# THERMO.net
KiCad netlist of a schematic drawn in Altium Designer
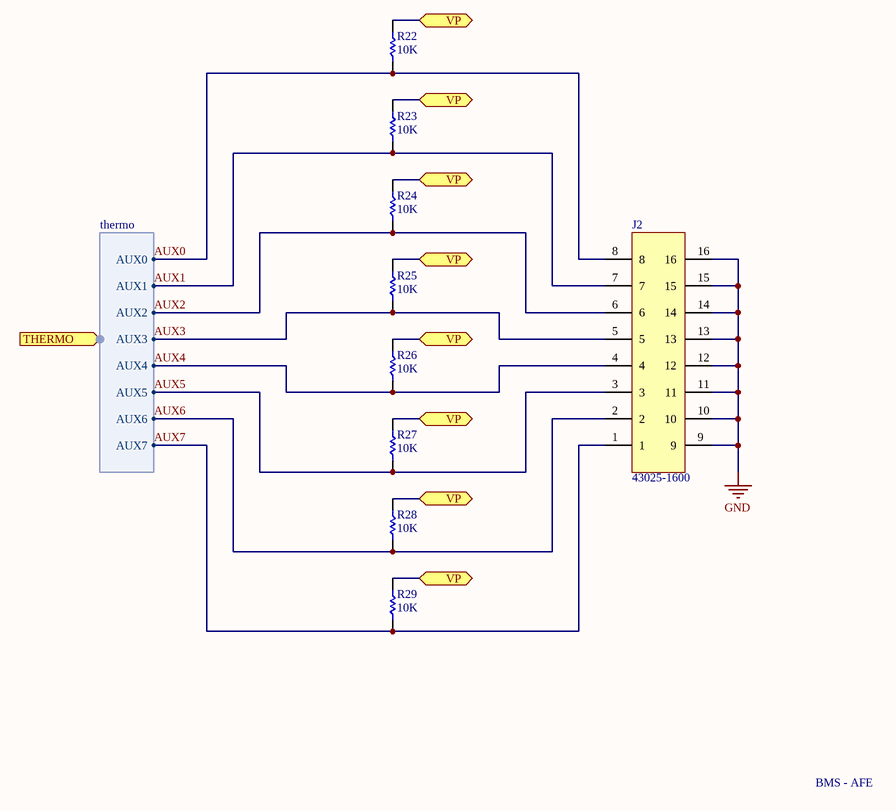
[diagram p0: THERMO.SchDoc]

(export (version "E")
  (design (tool "Eeschema 10.0.6"))
  (components
    (comp (ref "J2")
      (value "43025-1600")
      (footprint "THERMO HDR")
      (description "CONN RECEPT 16POS 3MM DUAL ROW")
      (fields (field (name "MANUFACTURER") "Molex"))
      (libsource (lib "parts") (part "43025-1600"))
    )
    (comp (ref "R22")
      (value "10K")
      (footprint "0603 RES")
      (description "RES SMD 10K OHM 1% 1/10W 0603")
      (fields
        (field (name "MANUFACTURER") "Panasonic")
        (field (name "MANUFACTURER PART NUMBER") "ERJ-3EKF1002V")
      )
      (libsource (lib "parts") (part "ERJ-3EKF1002V"))
    )
    (comp (ref "R23")
      (value "10K")
      (footprint "0603 RES")
      (description "RES SMD 10K OHM 1% 1/10W 0603")
      (fields
        (field (name "MANUFACTURER") "Panasonic")
        (field (name "MANUFACTURER PART NUMBER") "ERJ-3EKF1002V")
      )
      (libsource (lib "parts") (part "ERJ-3EKF1002V"))
    )
    (comp (ref "R24")
      (value "10K")
      (footprint "0603 RES")
      (description "RES SMD 10K OHM 1% 1/10W 0603")
      (fields
        (field (name "MANUFACTURER") "Panasonic")
        (field (name "MANUFACTURER PART NUMBER") "ERJ-3EKF1002V")
      )
      (libsource (lib "parts") (part "ERJ-3EKF1002V"))
    )
    (comp (ref "R25")
      (value "10K")
      (footprint "0603 RES")
      (description "RES SMD 10K OHM 1% 1/10W 0603")
      (fields
        (field (name "MANUFACTURER") "Panasonic")
        (field (name "MANUFACTURER PART NUMBER") "ERJ-3EKF1002V")
      )
      (libsource (lib "parts") (part "ERJ-3EKF1002V"))
    )
    (comp (ref "R26")
      (value "10K")
      (footprint "0603 RES")
      (description "RES SMD 10K OHM 1% 1/10W 0603")
      (fields
        (field (name "MANUFACTURER") "Panasonic")
        (field (name "MANUFACTURER PART NUMBER") "ERJ-3EKF1002V")
      )
      (libsource (lib "parts") (part "ERJ-3EKF1002V"))
    )
    (comp (ref "R27")
      (value "10K")
      (footprint "0603 RES")
      (description "RES SMD 10K OHM 1% 1/10W 0603")
      (fields
        (field (name "MANUFACTURER") "Panasonic")
        (field (name "MANUFACTURER PART NUMBER") "ERJ-3EKF1002V")
      )
      (libsource (lib "parts") (part "ERJ-3EKF1002V"))
    )
    (comp (ref "R28")
      (value "10K")
      (footprint "0603 RES")
      (description "RES SMD 10K OHM 1% 1/10W 0603")
      (fields
        (field (name "MANUFACTURER") "Panasonic")
        (field (name "MANUFACTURER PART NUMBER") "ERJ-3EKF1002V")
      )
      (libsource (lib "parts") (part "ERJ-3EKF1002V"))
    )
    (comp (ref "R29")
      (value "10K")
      (footprint "0603 RES")
      (description "RES SMD 10K OHM 1% 1/10W 0603")
      (fields
        (field (name "MANUFACTURER") "Panasonic")
        (field (name "MANUFACTURER PART NUMBER") "ERJ-3EKF1002V")
      )
      (libsource (lib "parts") (part "ERJ-3EKF1002V"))
    )
  )
  (nets
    (net (code "2") (name "/AUX0") (class "Default")
      (node (ref "J2") (pin "8") (pinfunction "8_8") (pintype "passive"))
      (node (ref "R22") (pin "1") (pinfunction "1_1") (pintype "passive"))
    )
    (net (code "3") (name "/AUX1") (class "Default")
      (node (ref "J2") (pin "7") (pinfunction "7_7") (pintype "passive"))
      (node (ref "R23") (pin "1") (pinfunction "1_1") (pintype "passive"))
    )
    (net (code "4") (name "/AUX2") (class "Default")
      (node (ref "J2") (pin "6") (pinfunction "6_6") (pintype "passive"))
      (node (ref "R24") (pin "1") (pinfunction "1_1") (pintype "passive"))
    )
    (net (code "5") (name "/AUX3") (class "Default")
      (node (ref "J2") (pin "5") (pinfunction "5_5") (pintype "passive"))
      (node (ref "R25") (pin "1") (pinfunction "1_1") (pintype "passive"))
    )
    (net (code "6") (name "/AUX4") (class "Default")
      (node (ref "J2") (pin "4") (pinfunction "4_4") (pintype "passive"))
      (node (ref "R26") (pin "1") (pinfunction "1_1") (pintype "passive"))
    )
    (net (code "7") (name "/AUX5") (class "Default")
      (node (ref "J2") (pin "3") (pinfunction "3_3") (pintype "passive"))
      (node (ref "R27") (pin "1") (pinfunction "1_1") (pintype "passive"))
    )
    (net (code "8") (name "/AUX6") (class "Default")
      (node (ref "J2") (pin "2") (pinfunction "2_2") (pintype "passive"))
      (node (ref "R28") (pin "1") (pinfunction "1_1") (pintype "passive"))
    )
    (net (code "9") (name "/AUX7") (class "Default")
      (node (ref "J2") (pin "1") (pinfunction "1_1") (pintype "passive"))
      (node (ref "R29") (pin "1") (pinfunction "1_1") (pintype "passive"))
    )
    (net (code "10") (name "/VP") (class "Default")
      (node (ref "R22") (pin "2") (pinfunction "2_2") (pintype "passive"))
      (node (ref "R23") (pin "2") (pinfunction "2_2") (pintype "passive"))
      (node (ref "R24") (pin "2") (pinfunction "2_2") (pintype "passive"))
      (node (ref "R25") (pin "2") (pinfunction "2_2") (pintype "passive"))
      (node (ref "R26") (pin "2") (pinfunction "2_2") (pintype "passive"))
      (node (ref "R27") (pin "2") (pinfunction "2_2") (pintype "passive"))
      (node (ref "R28") (pin "2") (pinfunction "2_2") (pintype "passive"))
      (node (ref "R29") (pin "2") (pinfunction "2_2") (pintype "passive"))
    )
    (net (code "12") (name "GND") (class "Default")
      (node (ref "J2") (pin "10") (pinfunction "10_10") (pintype "passive"))
      (node (ref "J2") (pin "11") (pinfunction "11_11") (pintype "passive"))
      (node (ref "J2") (pin "12") (pinfunction "12_12") (pintype "passive"))
      (node (ref "J2") (pin "13") (pinfunction "13_13") (pintype "passive"))
      (node (ref "J2") (pin "14") (pinfunction "14_14") (pintype "passive"))
      (node (ref "J2") (pin "15") (pinfunction "15_15") (pintype "passive"))
      (node (ref "J2") (pin "16") (pinfunction "16_16") (pintype "passive"))
      (node (ref "J2") (pin "9") (pinfunction "9_9") (pintype "passive"))
    )
  )
)
